# Sheet4_-_Capteurs.net
KiCad netlist of a schematic drawn in Altium Designer
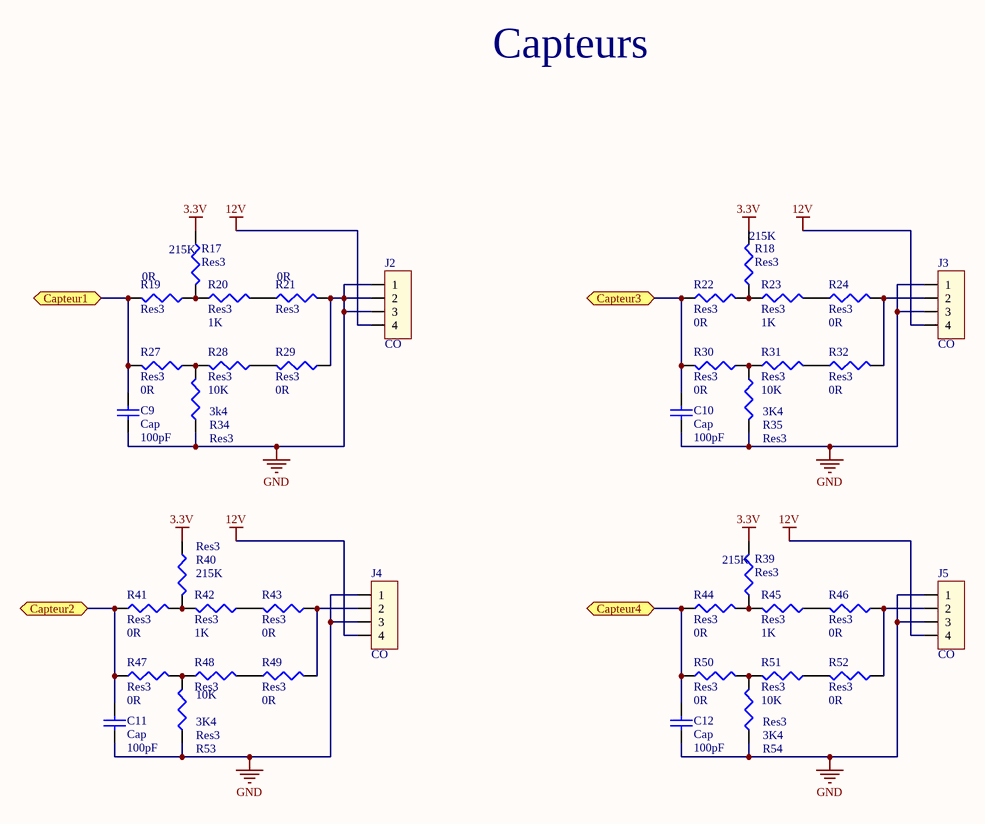
[diagram p0: Sheet4 - Capteurs.SchDoc]

(export (version "E")
  (design (tool "Eeschema 10.0.6"))
  (components
    (comp (ref "C9")
      (value "Cap")
      (footprint "RAD-0.3")
      (description "Capacitor")
      (fields (field (name "ALTIUM_VALUE") "100pF") (field (name "PUBLISHER") "Altium Limited"))
      (libsource (lib "Miscellaneous Devices") (part "Cap"))
    )
    (comp (ref "C10")
      (value "Cap")
      (footprint "RAD-0.3")
      (description "Capacitor")
      (fields (field (name "ALTIUM_VALUE") "100pF") (field (name "PUBLISHER") "Altium Limited"))
      (libsource (lib "Miscellaneous Devices") (part "Cap"))
    )
    (comp (ref "C11")
      (value "Cap")
      (footprint "RAD-0.3")
      (description "Capacitor")
      (fields (field (name "ALTIUM_VALUE") "100pF") (field (name "PUBLISHER") "Altium Limited"))
      (libsource (lib "Miscellaneous Devices") (part "Cap"))
    )
    (comp (ref "C12")
      (value "Cap")
      (footprint "RAD-0.3")
      (description "Capacitor")
      (fields (field (name "ALTIUM_VALUE") "100pF") (field (name "PUBLISHER") "Altium Limited"))
      (libsource (lib "Miscellaneous Devices") (part "Cap"))
    )
    (comp (ref "J2")
      (value "CO")
      (footprint "MICRO-MATCH FOB.04P")
      (description "Connecteur")
      (libsource (lib "lib_peb_1") (part "MICRO-MATCH FOB.04P"))
    )
    (comp (ref "J3")
      (value "CO")
      (footprint "MICRO-MATCH FOB.04P")
      (description "Connecteur")
      (libsource (lib "lib_peb_1") (part "MICRO-MATCH FOB.04P"))
    )
    (comp (ref "J4")
      (value "CO")
      (footprint "MICRO-MATCH FOB.04P")
      (description "Connecteur")
      (libsource (lib "lib_peb_1") (part "MICRO-MATCH FOB.04P"))
    )
    (comp (ref "J5")
      (value "CO")
      (footprint "MICRO-MATCH FOB.04P")
      (description "Connecteur")
      (libsource (lib "lib_peb_1") (part "MICRO-MATCH FOB.04P"))
    )
    (comp (ref "R17")
      (value "Res3")
      (footprint "RESC1608L")
      (description "Resistor")
      (fields (field (name "ALTIUM_VALUE") "215K") (field (name "PUBLISHER") "Altium Limited"))
      (libsource (lib "Miscellaneous Devices") (part "Res3"))
    )
    (comp (ref "R18")
      (value "Res3")
      (footprint "RESC1608L")
      (description "Resistor")
      (fields (field (name "ALTIUM_VALUE") "215K") (field (name "PUBLISHER") "Altium Limited"))
      (libsource (lib "Miscellaneous Devices") (part "Res3"))
    )
    (comp (ref "R19")
      (value "Res3")
      (footprint "RESC1608L")
      (description "Resistor")
      (fields (field (name "ALTIUM_VALUE") "0R") (field (name "PUBLISHER") "Altium Limited"))
      (libsource (lib "Miscellaneous Devices") (part "Res3"))
    )
    (comp (ref "R20")
      (value "Res3")
      (footprint "RESC1608L")
      (description "Resistor")
      (fields (field (name "ALTIUM_VALUE") "1K") (field (name "PUBLISHER") "Altium Limited"))
      (libsource (lib "Miscellaneous Devices") (part "Res3"))
    )
    (comp (ref "R21")
      (value "Res3")
      (footprint "RESC1608L")
      (description "Resistor")
      (fields (field (name "ALTIUM_VALUE") "0R") (field (name "PUBLISHER") "Altium Limited"))
      (libsource (lib "Miscellaneous Devices") (part "Res3"))
    )
    (comp (ref "R22")
      (value "Res3")
      (footprint "RESC1608L")
      (description "Resistor")
      (fields (field (name "ALTIUM_VALUE") "0R") (field (name "PUBLISHER") "Altium Limited"))
      (libsource (lib "Miscellaneous Devices") (part "Res3"))
    )
    (comp (ref "R23")
      (value "Res3")
      (footprint "RESC1608L")
      (description "Resistor")
      (fields (field (name "ALTIUM_VALUE") "1K") (field (name "PUBLISHER") "Altium Limited"))
      (libsource (lib "Miscellaneous Devices") (part "Res3"))
    )
    (comp (ref "R24")
      (value "Res3")
      (footprint "RESC1608L")
      (description "Resistor")
      (fields (field (name "ALTIUM_VALUE") "0R") (field (name "PUBLISHER") "Altium Limited"))
      (libsource (lib "Miscellaneous Devices") (part "Res3"))
    )
    (comp (ref "R27")
      (value "Res3")
      (footprint "RESC1608L")
      (description "Resistor")
      (fields (field (name "ALTIUM_VALUE") "0R") (field (name "PUBLISHER") "Altium Limited"))
      (libsource (lib "Miscellaneous Devices") (part "Res3"))
    )
    (comp (ref "R28")
      (value "Res3")
      (footprint "RESC1608L")
      (description "Resistor")
      (fields (field (name "ALTIUM_VALUE") "10K") (field (name "PUBLISHER") "Altium Limited"))
      (libsource (lib "Miscellaneous Devices") (part "Res3"))
    )
    (comp (ref "R29")
      (value "Res3")
      (footprint "RESC1608L")
      (description "Resistor")
      (fields (field (name "ALTIUM_VALUE") "0R") (field (name "PUBLISHER") "Altium Limited"))
      (libsource (lib "Miscellaneous Devices") (part "Res3"))
    )
    (comp (ref "R30")
      (value "Res3")
      (footprint "RESC1608L")
      (description "Resistor")
      (fields (field (name "ALTIUM_VALUE") "0R") (field (name "PUBLISHER") "Altium Limited"))
      (libsource (lib "Miscellaneous Devices") (part "Res3"))
    )
    (comp (ref "R31")
      (value "Res3")
      (footprint "RESC1608L")
      (description "Resistor")
      (fields (field (name "ALTIUM_VALUE") "10K") (field (name "PUBLISHER") "Altium Limited"))
      (libsource (lib "Miscellaneous Devices") (part "Res3"))
    )
    (comp (ref "R32")
      (value "Res3")
      (footprint "RESC1608L")
      (description "Resistor")
      (fields (field (name "ALTIUM_VALUE") "0R") (field (name "PUBLISHER") "Altium Limited"))
      (libsource (lib "Miscellaneous Devices") (part "Res3"))
    )
    (comp (ref "R34")
      (value "Res3")
      (footprint "RESC1608L")
      (description "Resistor")
      (fields (field (name "ALTIUM_VALUE") "3k4") (field (name "PUBLISHER") "Altium Limited"))
      (libsource (lib "Miscellaneous Devices") (part "Res3"))
    )
    (comp (ref "R35")
      (value "Res3")
      (footprint "RESC1608L")
      (description "Resistor")
      (fields (field (name "ALTIUM_VALUE") "3K4") (field (name "PUBLISHER") "Altium Limited"))
      (libsource (lib "Miscellaneous Devices") (part "Res3"))
    )
    (comp (ref "R39")
      (value "Res3")
      (footprint "RESC1608L")
      (description "Resistor")
      (fields (field (name "ALTIUM_VALUE") "215K") (field (name "PUBLISHER") "Altium Limited"))
      (libsource (lib "Miscellaneous Devices") (part "Res3"))
    )
    (comp (ref "R40")
      (value "Res3")
      (footprint "RESC1608L")
      (description "Resistor")
      (fields (field (name "ALTIUM_VALUE") "215K") (field (name "PUBLISHER") "Altium Limited"))
      (libsource (lib "Miscellaneous Devices") (part "Res3"))
    )
    (comp (ref "R41")
      (value "Res3")
      (footprint "RESC1608L")
      (description "Resistor")
      (fields (field (name "ALTIUM_VALUE") "0R") (field (name "PUBLISHER") "Altium Limited"))
      (libsource (lib "Miscellaneous Devices") (part "Res3"))
    )
    (comp (ref "R42")
      (value "Res3")
      (footprint "RESC1608L")
      (description "Resistor")
      (fields (field (name "ALTIUM_VALUE") "1K") (field (name "PUBLISHER") "Altium Limited"))
      (libsource (lib "Miscellaneous Devices") (part "Res3"))
    )
    (comp (ref "R43")
      (value "Res3")
      (footprint "RESC1608L")
      (description "Resistor")
      (fields (field (name "ALTIUM_VALUE") "0R") (field (name "PUBLISHER") "Altium Limited"))
      (libsource (lib "Miscellaneous Devices") (part "Res3"))
    )
    (comp (ref "R44")
      (value "Res3")
      (footprint "RESC1608L")
      (description "Resistor")
      (fields (field (name "ALTIUM_VALUE") "0R") (field (name "PUBLISHER") "Altium Limited"))
      (libsource (lib "Miscellaneous Devices") (part "Res3"))
    )
    (comp (ref "R45")
      (value "Res3")
      (footprint "RESC1608L")
      (description "Resistor")
      (fields (field (name "ALTIUM_VALUE") "1K") (field (name "PUBLISHER") "Altium Limited"))
      (libsource (lib "Miscellaneous Devices") (part "Res3"))
    )
    (comp (ref "R46")
      (value "Res3")
      (footprint "RESC1608L")
      (description "Resistor")
      (fields (field (name "ALTIUM_VALUE") "0R") (field (name "PUBLISHER") "Altium Limited"))
      (libsource (lib "Miscellaneous Devices") (part "Res3"))
    )
    (comp (ref "R47")
      (value "Res3")
      (footprint "RESC1608L")
      (description "Resistor")
      (fields (field (name "ALTIUM_VALUE") "0R") (field (name "PUBLISHER") "Altium Limited"))
      (libsource (lib "Miscellaneous Devices") (part "Res3"))
    )
    (comp (ref "R48")
      (value "Res3")
      (footprint "RESC1608L")
      (description "Resistor")
      (fields (field (name "ALTIUM_VALUE") "10K") (field (name "PUBLISHER") "Altium Limited"))
      (libsource (lib "Miscellaneous Devices") (part "Res3"))
    )
    (comp (ref "R49")
      (value "Res3")
      (footprint "RESC1608L")
      (description "Resistor")
      (fields (field (name "ALTIUM_VALUE") "0R") (field (name "PUBLISHER") "Altium Limited"))
      (libsource (lib "Miscellaneous Devices") (part "Res3"))
    )
    (comp (ref "R50")
      (value "Res3")
      (footprint "RESC1608L")
      (description "Resistor")
      (fields (field (name "ALTIUM_VALUE") "0R") (field (name "PUBLISHER") "Altium Limited"))
      (libsource (lib "Miscellaneous Devices") (part "Res3"))
    )
    (comp (ref "R51")
      (value "Res3")
      (footprint "RESC1608L")
      (description "Resistor")
      (fields (field (name "ALTIUM_VALUE") "10K") (field (name "PUBLISHER") "Altium Limited"))
      (libsource (lib "Miscellaneous Devices") (part "Res3"))
    )
    (comp (ref "R52")
      (value "Res3")
      (footprint "RESC1608L")
      (description "Resistor")
      (fields (field (name "ALTIUM_VALUE") "0R") (field (name "PUBLISHER") "Altium Limited"))
      (libsource (lib "Miscellaneous Devices") (part "Res3"))
    )
    (comp (ref "R53")
      (value "Res3")
      (footprint "RESC1608L")
      (description "Resistor")
      (fields (field (name "ALTIUM_VALUE") "3K4") (field (name "PUBLISHER") "Altium Limited"))
      (libsource (lib "Miscellaneous Devices") (part "Res3"))
    )
    (comp (ref "R54")
      (value "Res3")
      (footprint "RESC1608L")
      (description "Resistor")
      (fields (field (name "ALTIUM_VALUE") "3K4") (field (name "PUBLISHER") "Altium Limited"))
      (libsource (lib "Miscellaneous Devices") (part "Res3"))
    )
  )
  (nets
    (net (code "1") (name "/Capteur1") (class "Default")
      (node (ref "C9") (pin "1") (pinfunction "1_1") (pintype "passive"))
      (node (ref "R19") (pin "2") (pinfunction "2_2") (pintype "passive"))
      (node (ref "R27") (pin "2") (pinfunction "2_2") (pintype "passive"))
    )
    (net (code "2") (name "/Capteur2") (class "Default")
      (node (ref "C11") (pin "1") (pinfunction "1_1") (pintype "passive"))
      (node (ref "R41") (pin "1") (pinfunction "1_1") (pintype "passive"))
      (node (ref "R47") (pin "1") (pinfunction "1_1") (pintype "passive"))
    )
    (net (code "3") (name "/Capteur3") (class "Default")
      (node (ref "C10") (pin "1") (pinfunction "1_1") (pintype "passive"))
      (node (ref "R22") (pin "1") (pinfunction "1_1") (pintype "passive"))
      (node (ref "R30") (pin "2") (pinfunction "2_2") (pintype "passive"))
    )
    (net (code "4") (name "/Capteur4") (class "Default")
      (node (ref "C12") (pin "1") (pinfunction "1_1") (pintype "passive"))
      (node (ref "R44") (pin "1") (pinfunction "1_1") (pintype "passive"))
      (node (ref "R50") (pin "1") (pinfunction "1_1") (pintype "passive"))
    )
    (net (code "5") (name "3.3V") (class "Default")
      (node (ref "R17") (pin "1") (pinfunction "1_1") (pintype "passive"))
      (node (ref "R18") (pin "2") (pinfunction "2_2") (pintype "passive"))
      (node (ref "R39") (pin "2") (pinfunction "2_2") (pintype "passive"))
      (node (ref "R40") (pin "1") (pinfunction "1_1") (pintype "passive"))
    )
    (net (code "6") (name "12V") (class "Default")
      (node (ref "J2") (pin "4") (pinfunction "4_4") (pintype "passive"))
      (node (ref "J3") (pin "4") (pinfunction "4_4") (pintype "passive"))
      (node (ref "J4") (pin "4") (pinfunction "4_4") (pintype "passive"))
      (node (ref "J5") (pin "4") (pinfunction "4_4") (pintype "passive"))
    )
    (net (code "7") (name "GND") (class "Default")
      (node (ref "C10") (pin "2") (pinfunction "2_2") (pintype "passive"))
      (node (ref "C11") (pin "2") (pinfunction "2_2") (pintype "passive"))
      (node (ref "C12") (pin "2") (pinfunction "2_2") (pintype "passive"))
      (node (ref "C9") (pin "2") (pinfunction "2_2") (pintype "passive"))
      (node (ref "J2") (pin "1") (pinfunction "1_1") (pintype "passive"))
      (node (ref "J2") (pin "2") (pinfunction "2_2") (pintype "passive"))
      (node (ref "J2") (pin "3") (pinfunction "3_3") (pintype "passive"))
      (node (ref "J3") (pin "1") (pinfunction "1_1") (pintype "passive"))
      (node (ref "J3") (pin "3") (pinfunction "3_3") (pintype "passive"))
      (node (ref "J4") (pin "1") (pinfunction "1_1") (pintype "passive"))
      (node (ref "J4") (pin "3") (pinfunction "3_3") (pintype "passive"))
      (node (ref "J5") (pin "1") (pinfunction "1_1") (pintype "passive"))
      (node (ref "J5") (pin "3") (pinfunction "3_3") (pintype "passive"))
      (node (ref "R21") (pin "2") (pinfunction "2_2") (pintype "passive"))
      (node (ref "R29") (pin "1") (pinfunction "1_1") (pintype "passive"))
      (node (ref "R34") (pin "1") (pinfunction "1_1") (pintype "passive"))
      (node (ref "R35") (pin "2") (pinfunction "2_2") (pintype "passive"))
      (node (ref "R53") (pin "1") (pinfunction "1_1") (pintype "passive"))
      (node (ref "R54") (pin "1") (pinfunction "1_1") (pintype "passive"))
    )
    (net (code "8") (name "Net-(J3-Pad2)") (class "Default")
      (node (ref "J3") (pin "2") (pinfunction "2_2") (pintype "passive"))
      (node (ref "R24") (pin "2") (pinfunction "2_2") (pintype "passive"))
      (node (ref "R32") (pin "2") (pinfunction "2_2") (pintype "passive"))
    )
    (net (code "9") (name "Net-(J4-Pad2)") (class "Default")
      (node (ref "J4") (pin "2") (pinfunction "2_2") (pintype "passive"))
      (node (ref "R43") (pin "1") (pinfunction "1_1") (pintype "passive"))
      (node (ref "R49") (pin "2") (pinfunction "2_2") (pintype "passive"))
    )
    (net (code "10") (name "Net-(J5-Pad2)") (class "Default")
      (node (ref "J5") (pin "2") (pinfunction "2_2") (pintype "passive"))
      (node (ref "R46") (pin "1") (pinfunction "1_1") (pintype "passive"))
      (node (ref "R52") (pin "1") (pinfunction "1_1") (pintype "passive"))
    )
    (net (code "11") (name "Net-(R17-Pad2)") (class "Default")
      (node (ref "R17") (pin "2") (pinfunction "2_2") (pintype "passive"))
      (node (ref "R19") (pin "1") (pinfunction "1_1") (pintype "passive"))
      (node (ref "R20") (pin "1") (pinfunction "1_1") (pintype "passive"))
    )
    (net (code "12") (name "Net-(R18-Pad1)") (class "Default")
      (node (ref "R18") (pin "1") (pinfunction "1_1") (pintype "passive"))
      (node (ref "R22") (pin "2") (pinfunction "2_2") (pintype "passive"))
      (node (ref "R23") (pin "1") (pinfunction "1_1") (pintype "passive"))
    )
    (net (code "13") (name "Net-(R20-Pad2)") (class "Default")
      (node (ref "R20") (pin "2") (pinfunction "2_2") (pintype "passive"))
      (node (ref "R21") (pin "1") (pinfunction "1_1") (pintype "passive"))
    )
    (net (code "14") (name "Net-(R23-Pad2)") (class "Default")
      (node (ref "R23") (pin "2") (pinfunction "2_2") (pintype "passive"))
      (node (ref "R24") (pin "1") (pinfunction "1_1") (pintype "passive"))
    )
    (net (code "15") (name "Net-(R27-Pad1)") (class "Default")
      (node (ref "R27") (pin "1") (pinfunction "1_1") (pintype "passive"))
      (node (ref "R28") (pin "2") (pinfunction "2_2") (pintype "passive"))
      (node (ref "R34") (pin "2") (pinfunction "2_2") (pintype "passive"))
    )
    (net (code "16") (name "Net-(R28-Pad1)") (class "Default")
      (node (ref "R28") (pin "1") (pinfunction "1_1") (pintype "passive"))
      (node (ref "R29") (pin "2") (pinfunction "2_2") (pintype "passive"))
    )
    (net (code "17") (name "Net-(R30-Pad1)") (class "Default")
      (node (ref "R30") (pin "1") (pinfunction "1_1") (pintype "passive"))
      (node (ref "R31") (pin "1") (pinfunction "1_1") (pintype "passive"))
      (node (ref "R35") (pin "1") (pinfunction "1_1") (pintype "passive"))
    )
    (net (code "18") (name "Net-(R31-Pad2)") (class "Default")
      (node (ref "R31") (pin "2") (pinfunction "2_2") (pintype "passive"))
      (node (ref "R32") (pin "1") (pinfunction "1_1") (pintype "passive"))
    )
    (net (code "19") (name "Net-(R39-Pad1)") (class "Default")
      (node (ref "R39") (pin "1") (pinfunction "1_1") (pintype "passive"))
      (node (ref "R44") (pin "2") (pinfunction "2_2") (pintype "passive"))
      (node (ref "R45") (pin "2") (pinfunction "2_2") (pintype "passive"))
    )
    (net (code "20") (name "Net-(R40-Pad2)") (class "Default")
      (node (ref "R40") (pin "2") (pinfunction "2_2") (pintype "passive"))
      (node (ref "R41") (pin "2") (pinfunction "2_2") (pintype "passive"))
      (node (ref "R42") (pin "2") (pinfunction "2_2") (pintype "passive"))
    )
    (net (code "21") (name "Net-(R42-Pad1)") (class "Default")
      (node (ref "R42") (pin "1") (pinfunction "1_1") (pintype "passive"))
      (node (ref "R43") (pin "2") (pinfunction "2_2") (pintype "passive"))
    )
    (net (code "22") (name "Net-(R45-Pad1)") (class "Default")
      (node (ref "R45") (pin "1") (pinfunction "1_1") (pintype "passive"))
      (node (ref "R46") (pin "2") (pinfunction "2_2") (pintype "passive"))
    )
    (net (code "23") (name "Net-(R47-Pad2)") (class "Default")
      (node (ref "R47") (pin "2") (pinfunction "2_2") (pintype "passive"))
      (node (ref "R48") (pin "1") (pinfunction "1_1") (pintype "passive"))
      (node (ref "R53") (pin "2") (pinfunction "2_2") (pintype "passive"))
    )
    (net (code "24") (name "Net-(R48-Pad2)") (class "Default")
      (node (ref "R48") (pin "2") (pinfunction "2_2") (pintype "passive"))
      (node (ref "R49") (pin "1") (pinfunction "1_1") (pintype "passive"))
    )
    (net (code "25") (name "Net-(R50-Pad2)") (class "Default")
      (node (ref "R50") (pin "2") (pinfunction "2_2") (pintype "passive"))
      (node (ref "R51") (pin "2") (pinfunction "2_2") (pintype "passive"))
      (node (ref "R54") (pin "2") (pinfunction "2_2") (pintype "passive"))
    )
    (net (code "26") (name "Net-(R51-Pad1)") (class "Default")
      (node (ref "R51") (pin "1") (pinfunction "1_1") (pintype "passive"))
      (node (ref "R52") (pin "2") (pinfunction "2_2") (pintype "passive"))
    )
  )
)
